# 07_USB_Interface.net
KiCad netlist of a schematic drawn in Altium Designer
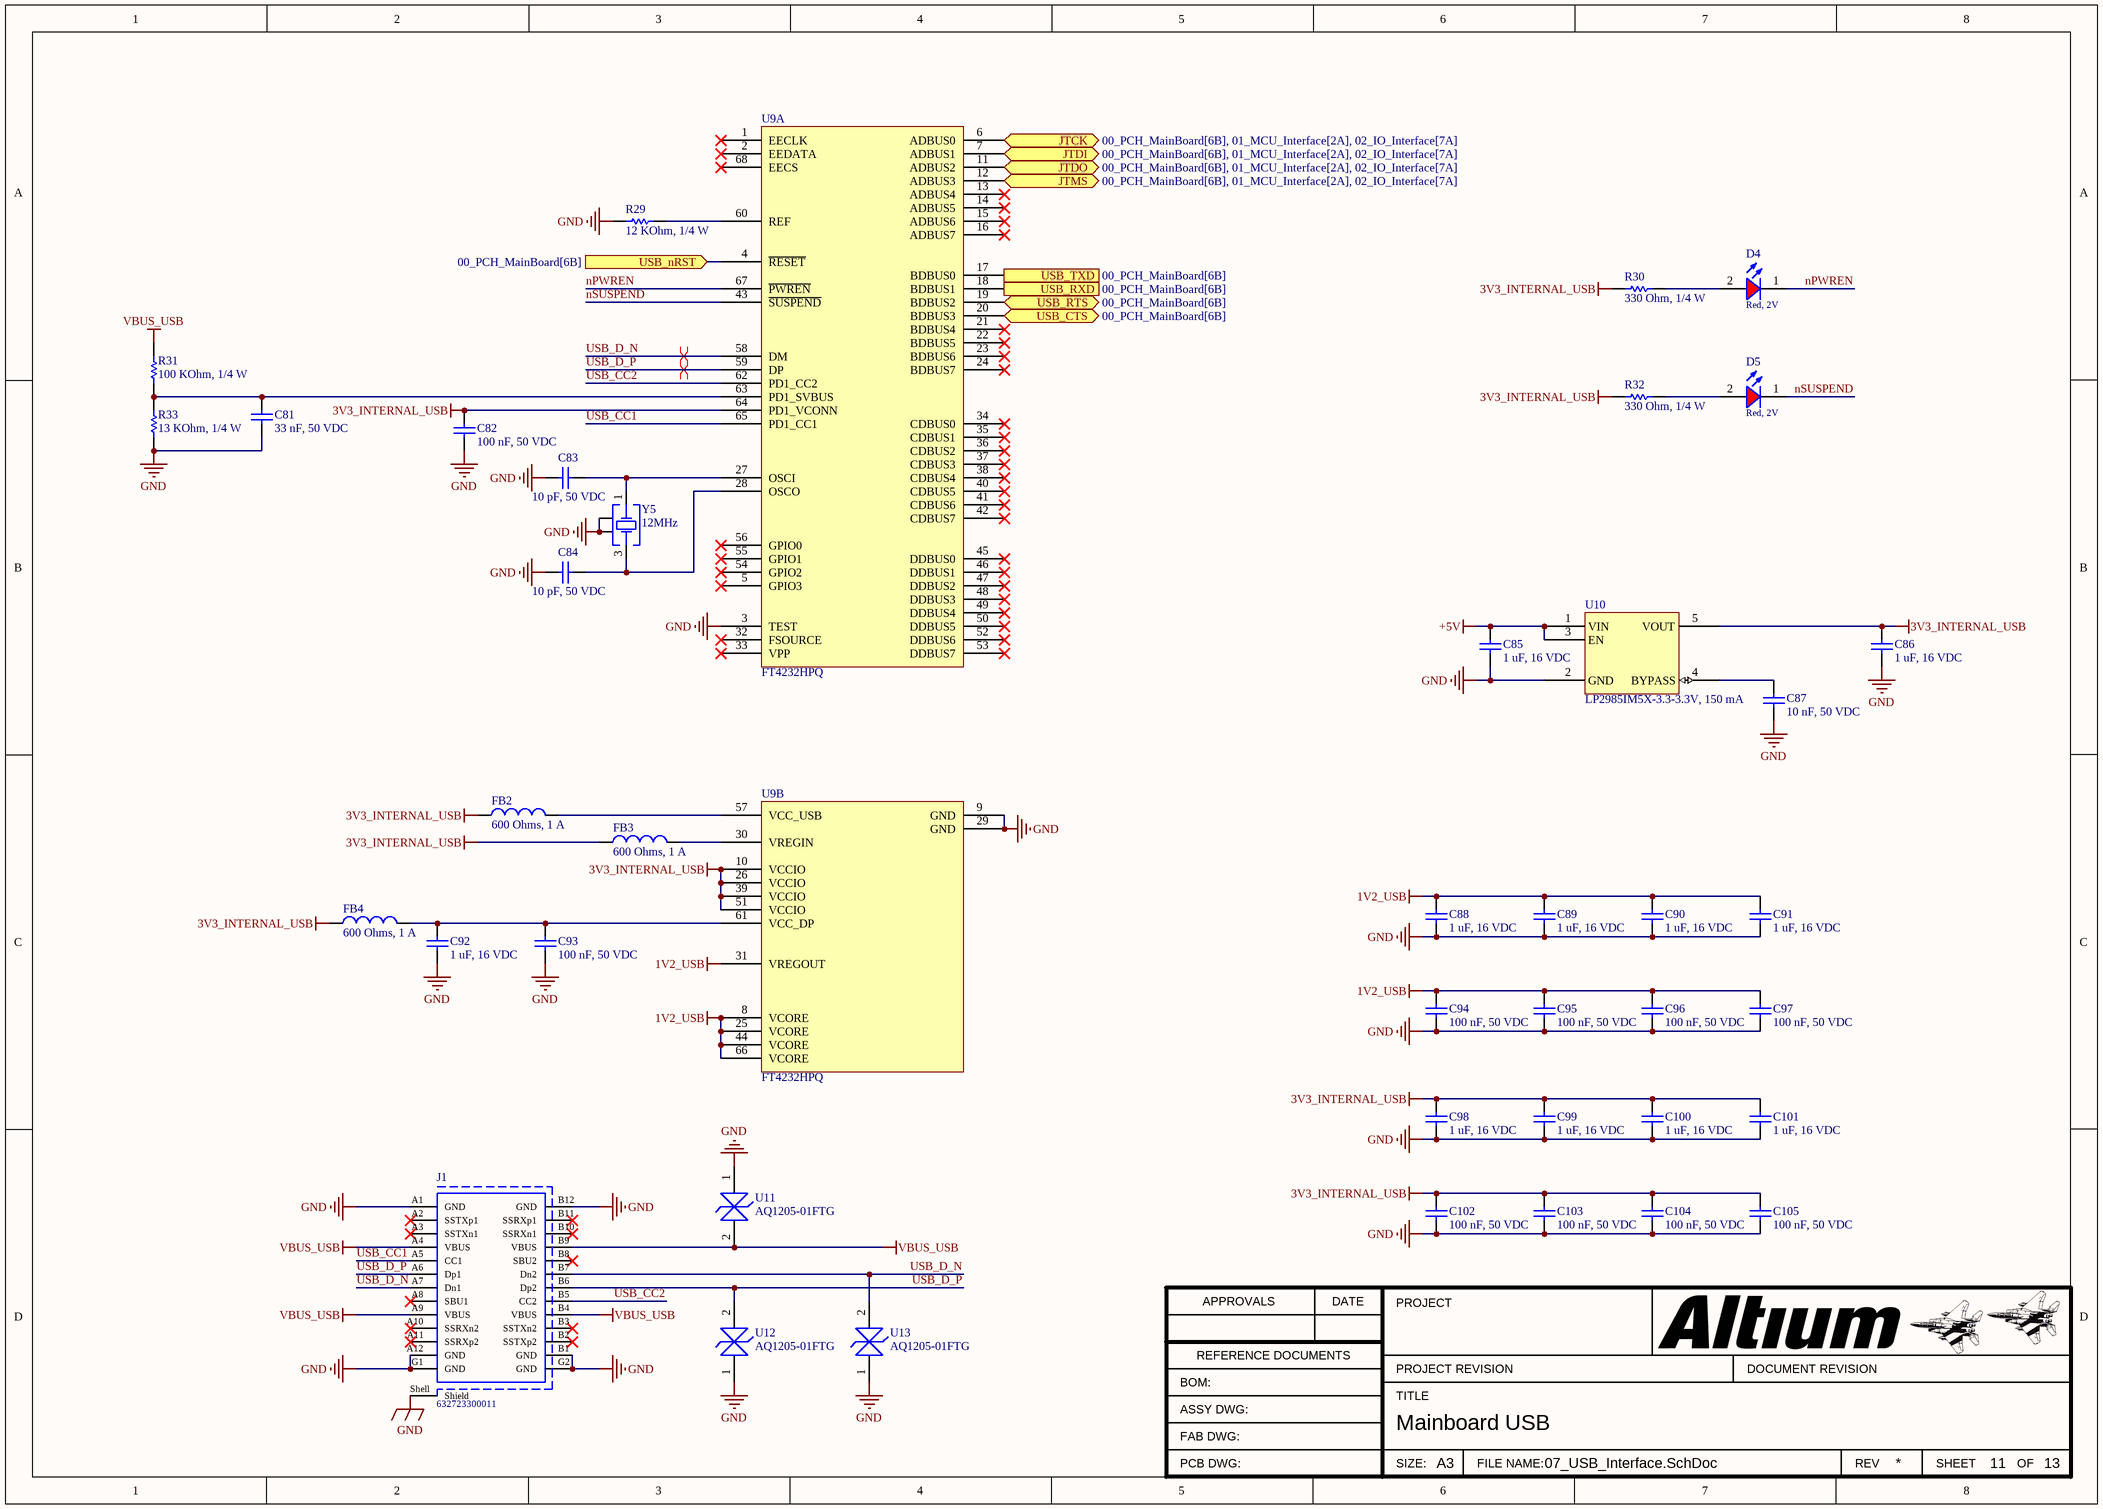
[diagram p0: 07_USB_Interface.SchDoc]

(export (version "E")
  (design (tool "Eeschema 10.0.6"))
  (components
    (comp (ref "C81")
      (value "33 nF, 50 VDC")
      (footprint "CAP_0603")
      (description "CAP, size 0603, 33 nF, 50 VDC")
      (fields (field (name "TOLERANCE") "+/-10%"))
      (libsource (lib "Altium_Ceramic_Cap") (part "0106033331050"))
    )
    (comp (ref "C82")
      (value "100 nF, 50 VDC")
      (footprint "CAP_0603")
      (description "CAP, size 0603, 100 nF, 50 VDC")
      (fields (field (name "TOLERANCE") "+/-10%"))
      (libsource (lib "Altium_Ceramic_Cap") (part "0106031041050"))
    )
    (comp (ref "C83")
      (value "10 pF, 50 VDC")
      (footprint "CAP_0603")
      (description "CAP, size 0603, 10 pF, 50 VDC")
      (fields (field (name "TOLERANCE") "+/-5%"))
      (libsource (lib "Altium_Ceramic_Cap") (part "0106031000550"))
    )
    (comp (ref "C84")
      (value "10 pF, 50 VDC")
      (footprint "CAP_0603")
      (description "CAP, size 0603, 10 pF, 50 VDC")
      (fields (field (name "TOLERANCE") "+/-5%"))
      (libsource (lib "Altium_Ceramic_Cap") (part "0106031000550"))
    )
    (comp (ref "C85")
      (value "1 uF, 16 VDC")
      (footprint "CAP_0603")
      (description "CAP, size 0603, 1 uF, 16 VDC")
      (fields (field (name "TOLERANCE") "+/-10%"))
      (libsource (lib "Altium_Ceramic_Cap") (part "0106031051016"))
    )
    (comp (ref "C86")
      (value "1 uF, 16 VDC")
      (footprint "CAP_0603")
      (description "CAP, size 0603, 1 uF, 16 VDC")
      (fields (field (name "TOLERANCE") "+/-10%"))
      (libsource (lib "Altium_Ceramic_Cap") (part "0106031051016"))
    )
    (comp (ref "C87")
      (value "10 nF, 50 VDC")
      (footprint "CAP_0603")
      (description "CAP, size 0603, 10 nF, 50 VDC")
      (fields (field (name "TOLERANCE") "+/-5%"))
      (libsource (lib "Altium_Ceramic_Cap") (part "0106031030550"))
    )
    (comp (ref "C88")
      (value "1 uF, 16 VDC")
      (footprint "CAP_0603")
      (description "CAP, size 0603, 1 uF, 16 VDC")
      (fields (field (name "TOLERANCE") "+/-10%"))
      (libsource (lib "Altium_Ceramic_Cap") (part "0106031051016"))
    )
    (comp (ref "C89")
      (value "1 uF, 16 VDC")
      (footprint "CAP_0603")
      (description "CAP, size 0603, 1 uF, 16 VDC")
      (fields (field (name "TOLERANCE") "+/-10%"))
      (libsource (lib "Altium_Ceramic_Cap") (part "0106031051016"))
    )
    (comp (ref "C90")
      (value "1 uF, 16 VDC")
      (footprint "CAP_0603")
      (description "CAP, size 0603, 1 uF, 16 VDC")
      (fields (field (name "TOLERANCE") "+/-10%"))
      (libsource (lib "Altium_Ceramic_Cap") (part "0106031051016"))
    )
    (comp (ref "C91")
      (value "1 uF, 16 VDC")
      (footprint "CAP_0603")
      (description "CAP, size 0603, 1 uF, 16 VDC")
      (fields (field (name "TOLERANCE") "+/-10%"))
      (libsource (lib "Altium_Ceramic_Cap") (part "0106031051016"))
    )
    (comp (ref "C92")
      (value "1 uF, 16 VDC")
      (footprint "CAP_0603")
      (description "CAP, size 0603, 1 uF, 16 VDC")
      (fields (field (name "TOLERANCE") "+/-10%"))
      (libsource (lib "Altium_Ceramic_Cap") (part "0106031051016"))
    )
    (comp (ref "C93")
      (value "100 nF, 50 VDC")
      (footprint "CAP_0603")
      (description "CAP, size 0603, 100 nF, 50 VDC")
      (fields (field (name "TOLERANCE") "+/-10%"))
      (libsource (lib "Altium_Ceramic_Cap") (part "0106031041050"))
    )
    (comp (ref "C94")
      (value "100 nF, 50 VDC")
      (footprint "CAP_0603")
      (description "CAP, size 0603, 100 nF, 50 VDC")
      (fields (field (name "TOLERANCE") "+/-10%"))
      (libsource (lib "Altium_Ceramic_Cap") (part "0106031041050"))
    )
    (comp (ref "C95")
      (value "100 nF, 50 VDC")
      (footprint "CAP_0603")
      (description "CAP, size 0603, 100 nF, 50 VDC")
      (fields (field (name "TOLERANCE") "+/-10%"))
      (libsource (lib "Altium_Ceramic_Cap") (part "0106031041050"))
    )
    (comp (ref "C96")
      (value "100 nF, 50 VDC")
      (footprint "CAP_0603")
      (description "CAP, size 0603, 100 nF, 50 VDC")
      (fields (field (name "TOLERANCE") "+/-10%"))
      (libsource (lib "Altium_Ceramic_Cap") (part "0106031041050"))
    )
    (comp (ref "C97")
      (value "100 nF, 50 VDC")
      (footprint "CAP_0603")
      (description "CAP, size 0603, 100 nF, 50 VDC")
      (fields (field (name "TOLERANCE") "+/-10%"))
      (libsource (lib "Altium_Ceramic_Cap") (part "0106031041050"))
    )
    (comp (ref "C98")
      (value "1 uF, 16 VDC")
      (footprint "CAP_0603")
      (description "CAP, size 0603, 1 uF, 16 VDC")
      (fields (field (name "TOLERANCE") "+/-10%"))
      (libsource (lib "Altium_Ceramic_Cap") (part "0106031051016"))
    )
    (comp (ref "C99")
      (value "1 uF, 16 VDC")
      (footprint "CAP_0603")
      (description "CAP, size 0603, 1 uF, 16 VDC")
      (fields (field (name "TOLERANCE") "+/-10%"))
      (libsource (lib "Altium_Ceramic_Cap") (part "0106031051016"))
    )
    (comp (ref "C100")
      (value "1 uF, 16 VDC")
      (footprint "CAP_0603")
      (description "CAP, size 0603, 1 uF, 16 VDC")
      (fields (field (name "TOLERANCE") "+/-10%"))
      (libsource (lib "Altium_Ceramic_Cap") (part "0106031051016"))
    )
    (comp (ref "C101")
      (value "1 uF, 16 VDC")
      (footprint "CAP_0603")
      (description "CAP, size 0603, 1 uF, 16 VDC")
      (fields (field (name "TOLERANCE") "+/-10%"))
      (libsource (lib "Altium_Ceramic_Cap") (part "0106031051016"))
    )
    (comp (ref "C102")
      (value "100 nF, 50 VDC")
      (footprint "CAP_0603")
      (description "CAP, size 0603, 100 nF, 50 VDC")
      (fields (field (name "TOLERANCE") "+/-10%"))
      (libsource (lib "Altium_Ceramic_Cap") (part "0106031041050"))
    )
    (comp (ref "C103")
      (value "100 nF, 50 VDC")
      (footprint "CAP_0603")
      (description "CAP, size 0603, 100 nF, 50 VDC")
      (fields (field (name "TOLERANCE") "+/-10%"))
      (libsource (lib "Altium_Ceramic_Cap") (part "0106031041050"))
    )
    (comp (ref "C104")
      (value "100 nF, 50 VDC")
      (footprint "CAP_0603")
      (description "CAP, size 0603, 100 nF, 50 VDC")
      (fields (field (name "TOLERANCE") "+/-10%"))
      (libsource (lib "Altium_Ceramic_Cap") (part "0106031041050"))
    )
    (comp (ref "C105")
      (value "100 nF, 50 VDC")
      (footprint "CAP_0603")
      (description "CAP, size 0603, 100 nF, 50 VDC")
      (fields (field (name "TOLERANCE") "+/-10%"))
      (libsource (lib "Altium_Ceramic_Cap") (part "0106031041050"))
    )
    (comp (ref "D4")
      (value "Red, 2V")
      (footprint "WL-SMCW_0603_H=0.7mm")
      (description "WL-SMCW SMT Mono-color Chip LED Blur, size 0603, Red, 2V, 140deg")
      (libsource (lib "Altium_LED") (part "160603RedBlur"))
    )
    (comp (ref "D5")
      (value "Red, 2V")
      (footprint "WL-SMCW_0603_H=0.7mm")
      (description "WL-SMCW SMT Mono-color Chip LED Blur, size 0603, Red, 2V, 140deg")
      (libsource (lib "Altium_LED") (part "160603RedBlur"))
    )
    (comp (ref "FB2")
      (value "600 Ohms, 1 A")
      (footprint "FER_0603")
      (description "Ferrite, 0603, 600 Ohms, 1 A")
      (fields (field (name "TOLERANCE") "+/-25%"))
      (libsource (lib "Altium_Ferrite_Bead") (part "03060360110225"))
    )
    (comp (ref "FB3")
      (value "600 Ohms, 1 A")
      (footprint "FER_0603")
      (description "Ferrite, 0603, 600 Ohms, 1 A")
      (fields (field (name "TOLERANCE") "+/-25%"))
      (libsource (lib "Altium_Ferrite_Bead") (part "03060360110225"))
    )
    (comp (ref "FB4")
      (value "600 Ohms, 1 A")
      (footprint "FER_0603")
      (description "Ferrite, 0603, 600 Ohms, 1 A")
      (fields (field (name "TOLERANCE") "+/-25%"))
      (libsource (lib "Altium_Ferrite_Bead") (part "03060360110225"))
    )
    (comp (ref "J1")
      (value "632723300011")
      (footprint "632723300011")
      (description "USB 3.1 Type C Receptacle WR-COM, Horizontal, SMT / THT")
      (fields (field (name "PUBLISHER") "Wurth Elektronik"))
      (libsource (lib "Altium_USB") (part "632723300011"))
    )
    (comp (ref "R29")
      (value "12 KOhm, 1/4 W")
      (footprint "resistor_0603")
      (description "RES, size 0603, 12 KOhm, 1/4 W")
      (libsource (lib "Altium_Resistor") (part "0006031231"))
    )
    (comp (ref "R30")
      (value "330 Ohm, 1/4 W")
      (footprint "resistor_0603")
      (description "RES, size 0603, 330 Ohm, 1/4 W")
      (libsource (lib "Altium_Resistor") (part "0006033311"))
    )
    (comp (ref "R31")
      (value "100 KOhm, 1/4 W")
      (footprint "resistor_0603")
      (description "RES, size 0603, 100 KOhm, 1/4 W")
      (libsource (lib "Altium_Resistor") (part "0006031041"))
    )
    (comp (ref "R32")
      (value "330 Ohm, 1/4 W")
      (footprint "resistor_0603")
      (description "RES, size 0603, 330 Ohm, 1/4 W")
      (libsource (lib "Altium_Resistor") (part "0006033311"))
    )
    (comp (ref "R33")
      (value "13 KOhm, 1/4 W")
      (footprint "resistor_0603")
      (description "RES, size 0603, 13 KOhm, 1/4 W")
      (libsource (lib "Altium_Resistor") (part "0006031331"))
    )
    (comp (ref "U9")
      (value "FT4232HPQ")
      (footprint "FT4232HPQ")
      (description "USB Interface IC USB Bridge Type-C 3.0 32-Bit 8kB 48kB")
      (fields (field (name "MANUFACTURER") "FTDI"))
      (libsource (lib "Altium_MCU") (part "FT4232HPQ"))
    )
    (comp (ref "U10")
      (value "LP2985IM5X-3.3-3.3V, 150 mA")
      (footprint "SOT23-5")
      (description "Out: 3.3V, 150 mA max; In: 2.5 V to 16 V; Pacakge: SOT-23-5")
      (fields
        (field (name "MANUFACTURER") "Texas Instruments")
        (field (name "MANUFACTURER PART NUMBER") "LP2985IM5X-3.3")
      )
      (libsource (lib "Altium_Power_Supply_IC") (part "LP2985IM5X-3.3/NOPBSOT23"))
    )
    (comp (ref "U11")
      (value "AQ1205-01FTG")
      (footprint "SOD323")
      (description "ESD Suppressors / TVS Diodes 5V 7A 30kV SOD323 Bi-dir TVS")
      (libsource (lib "Altium_ESD") (part "AQ1205-01FTG"))
    )
    (comp (ref "U12")
      (value "AQ1205-01FTG")
      (footprint "SOD323")
      (description "ESD Suppressors / TVS Diodes 5V 7A 30kV SOD323 Bi-dir TVS")
      (libsource (lib "Altium_ESD") (part "AQ1205-01FTG"))
    )
    (comp (ref "U13")
      (value "AQ1205-01FTG")
      (footprint "SOD323")
      (description "ESD Suppressors / TVS Diodes 5V 7A 30kV SOD323 Bi-dir TVS")
      (libsource (lib "Altium_ESD") (part "AQ1205-01FTG"))
    )
    (comp (ref "Y5")
      (value "12MHz")
      (footprint "WE-XTAL_CFPX-180")
      (description "WE-XTAL Quartz Crystal, SMT, CFPX-180, 12MHz, +/-30ppm")
      (fields
        (field (name "MANUFACTURER PART NUMBER") "NX3225SA-12MHZ-STD-CSR-6")
        (field (name "MANUFACTURER") "NDK")
      )
      (libsource (lib "Altium_XTAL") (part "073525126010"))
    )
  )
  (nets
    (net (code "1") (name "+5V") (class "Default")
      (node (ref "C85") (pin "2") (pinfunction "2_2") (pintype "passive"))
      (node (ref "U10") (pin "1") (pinfunction "VIN_1") (pintype "power_in"))
      (node (ref "U10") (pin "3") (pinfunction "EN_3") (pintype "passive"))
    )
    (net (code "2") (name "/JTCK") (class "Default")
      (node (ref "U9") (pin "6") (pinfunction "ADBUS0_6") (pintype "passive"))
    )
    (net (code "3") (name "/JTDI") (class "Default")
      (node (ref "U9") (pin "7") (pinfunction "ADBUS1_7") (pintype "passive"))
    )
    (net (code "4") (name "/JTDO") (class "Default")
      (node (ref "U9") (pin "11") (pinfunction "ADBUS2_11") (pintype "passive"))
    )
    (net (code "5") (name "/JTMS") (class "Default")
      (node (ref "U9") (pin "12") (pinfunction "ADBUS3_12") (pintype "passive"))
    )
    (net (code "6") (name "/USB_CC1") (class "Default")
      (node (ref "J1") (pin "A5") (pinfunction "CC1_A5") (pintype "passive"))
      (node (ref "U9") (pin "65") (pinfunction "PD1_CC1_65") (pintype "passive"))
    )
    (net (code "7") (name "/USB_CC2") (class "Default")
      (node (ref "J1") (pin "B5") (pinfunction "CC2_B5") (pintype "passive"))
      (node (ref "U9") (pin "62") (pinfunction "PD1_CC2_62") (pintype "passive"))
    )
    (net (code "8") (name "/USB_CTS") (class "Default")
      (node (ref "U9") (pin "20") (pinfunction "BDBUS3_20") (pintype "passive"))
    )
    (net (code "9") (name "/USB_D_N") (class "Default")
      (node (ref "J1") (pin "A7") (pinfunction "Dn1_A7") (pintype "passive"))
      (node (ref "J1") (pin "B7") (pinfunction "Dn2_B7") (pintype "passive"))
      (node (ref "U13") (pin "2") (pinfunction "2_2") (pintype "passive"))
      (node (ref "U9") (pin "58") (pinfunction "DM_58") (pintype "passive"))
    )
    (net (code "10") (name "/USB_D_P") (class "Default")
      (node (ref "J1") (pin "A6") (pinfunction "Dp1_A6") (pintype "passive"))
      (node (ref "J1") (pin "B6") (pinfunction "Dp2_B6") (pintype "passive"))
      (node (ref "U12") (pin "2") (pinfunction "2_2") (pintype "passive"))
      (node (ref "U9") (pin "59") (pinfunction "DP_59") (pintype "passive"))
    )
    (net (code "11") (name "/USB_RTS") (class "Default")
      (node (ref "U9") (pin "19") (pinfunction "BDBUS2_19") (pintype "passive"))
    )
    (net (code "12") (name "/USB_RXD") (class "Default")
      (node (ref "U9") (pin "18") (pinfunction "BDBUS1_18") (pintype "passive"))
    )
    (net (code "13") (name "/USB_TXD") (class "Default")
      (node (ref "U9") (pin "17") (pinfunction "BDBUS0_17") (pintype "passive"))
    )
    (net (code "14") (name "/USB_nRST") (class "Default")
      (node (ref "U9") (pin "4") (pinfunction "~{RESET}_4") (pintype "passive"))
    )
    (net (code "15") (name "/nPWREN") (class "Default")
      (node (ref "D4") (pin "1") (pinfunction "K_1") (pintype "passive"))
      (node (ref "U9") (pin "67") (pinfunction "~{PWREN}_67") (pintype "passive"))
    )
    (net (code "16") (name "/nSUSPEND") (class "Default")
      (node (ref "D5") (pin "1") (pinfunction "K_1") (pintype "passive"))
      (node (ref "U9") (pin "43") (pinfunction "~{SUSPEND}_43") (pintype "passive"))
    )
    (net (code "17") (name "1V2_USB") (class "Default")
      (node (ref "C88") (pin "2") (pinfunction "2_2") (pintype "passive"))
      (node (ref "C89") (pin "2") (pinfunction "2_2") (pintype "passive"))
      (node (ref "C90") (pin "2") (pinfunction "2_2") (pintype "passive"))
      (node (ref "C91") (pin "2") (pinfunction "2_2") (pintype "passive"))
      (node (ref "C94") (pin "2") (pinfunction "2_2") (pintype "passive"))
      (node (ref "C95") (pin "2") (pinfunction "2_2") (pintype "passive"))
      (node (ref "C96") (pin "2") (pinfunction "2_2") (pintype "passive"))
      (node (ref "C97") (pin "2") (pinfunction "2_2") (pintype "passive"))
      (node (ref "U9") (pin "25") (pinfunction "VCORE_25") (pintype "passive"))
      (node (ref "U9") (pin "31") (pinfunction "VREGOUT_31") (pintype "passive"))
      (node (ref "U9") (pin "44") (pinfunction "VCORE_44") (pintype "passive"))
      (node (ref "U9") (pin "66") (pinfunction "VCORE_66") (pintype "passive"))
      (node (ref "U9") (pin "8") (pinfunction "VCORE_8") (pintype "passive"))
    )
    (net (code "18") (name "3V3_INTERNAL_USB") (class "Default")
      (node (ref "C100") (pin "2") (pinfunction "2_2") (pintype "passive"))
      (node (ref "C101") (pin "2") (pinfunction "2_2") (pintype "passive"))
      (node (ref "C102") (pin "2") (pinfunction "2_2") (pintype "passive"))
      (node (ref "C103") (pin "2") (pinfunction "2_2") (pintype "passive"))
      (node (ref "C104") (pin "2") (pinfunction "2_2") (pintype "passive"))
      (node (ref "C105") (pin "2") (pinfunction "2_2") (pintype "passive"))
      (node (ref "C82") (pin "2") (pinfunction "2_2") (pintype "passive"))
      (node (ref "C86") (pin "2") (pinfunction "2_2") (pintype "passive"))
      (node (ref "C98") (pin "2") (pinfunction "2_2") (pintype "passive"))
      (node (ref "C99") (pin "2") (pinfunction "2_2") (pintype "passive"))
      (node (ref "FB2") (pin "1") (pinfunction "1_1") (pintype "passive"))
      (node (ref "FB3") (pin "1") (pinfunction "1_1") (pintype "passive"))
      (node (ref "FB4") (pin "1") (pinfunction "1_1") (pintype "passive"))
      (node (ref "R30") (pin "2") (pinfunction "2_2") (pintype "passive"))
      (node (ref "R32") (pin "2") (pinfunction "2_2") (pintype "passive"))
      (node (ref "U10") (pin "5") (pinfunction "VOUT_5") (pintype "power_in"))
      (node (ref "U9") (pin "10") (pinfunction "VCCIO_10") (pintype "passive"))
      (node (ref "U9") (pin "26") (pinfunction "VCCIO_26") (pintype "passive"))
      (node (ref "U9") (pin "39") (pinfunction "VCCIO_39") (pintype "passive"))
      (node (ref "U9") (pin "51") (pinfunction "VCCIO_51") (pintype "passive"))
      (node (ref "U9") (pin "64") (pinfunction "PD1_VCONN_64") (pintype "passive"))
    )
    (net (code "19") (name "GND") (class "Default")
      (node (ref "C100") (pin "1") (pinfunction "1_1") (pintype "passive"))
      (node (ref "C101") (pin "1") (pinfunction "1_1") (pintype "passive"))
      (node (ref "C102") (pin "1") (pinfunction "1_1") (pintype "passive"))
      (node (ref "C103") (pin "1") (pinfunction "1_1") (pintype "passive"))
      (node (ref "C104") (pin "1") (pinfunction "1_1") (pintype "passive"))
      (node (ref "C105") (pin "1") (pinfunction "1_1") (pintype "passive"))
      (node (ref "C81") (pin "1") (pinfunction "1_1") (pintype "passive"))
      (node (ref "C82") (pin "1") (pinfunction "1_1") (pintype "passive"))
      (node (ref "C83") (pin "1") (pinfunction "1_1") (pintype "passive"))
      (node (ref "C84") (pin "1") (pinfunction "1_1") (pintype "passive"))
      (node (ref "C85") (pin "1") (pinfunction "1_1") (pintype "passive"))
      (node (ref "C86") (pin "1") (pinfunction "1_1") (pintype "passive"))
      (node (ref "C87") (pin "1") (pinfunction "1_1") (pintype "passive"))
      (node (ref "C88") (pin "1") (pinfunction "1_1") (pintype "passive"))
      (node (ref "C89") (pin "1") (pinfunction "1_1") (pintype "passive"))
      (node (ref "C90") (pin "1") (pinfunction "1_1") (pintype "passive"))
      (node (ref "C91") (pin "1") (pinfunction "1_1") (pintype "passive"))
      (node (ref "C92") (pin "1") (pinfunction "1_1") (pintype "passive"))
      (node (ref "C93") (pin "1") (pinfunction "1_1") (pintype "passive"))
      (node (ref "C94") (pin "1") (pinfunction "1_1") (pintype "passive"))
      (node (ref "C95") (pin "1") (pinfunction "1_1") (pintype "passive"))
      (node (ref "C96") (pin "1") (pinfunction "1_1") (pintype "passive"))
      (node (ref "C97") (pin "1") (pinfunction "1_1") (pintype "passive"))
      (node (ref "C98") (pin "1") (pinfunction "1_1") (pintype "passive"))
      (node (ref "C99") (pin "1") (pinfunction "1_1") (pintype "passive"))
      (node (ref "J1") (pin "A1") (pinfunction "GND_A1") (pintype "passive"))
      (node (ref "J1") (pin "A12") (pinfunction "GND_A12") (pintype "passive"))
      (node (ref "J1") (pin "B1") (pinfunction "GND_B1") (pintype "passive"))
      (node (ref "J1") (pin "B12") (pinfunction "GND_B12") (pintype "passive"))
      (node (ref "J1") (pin "G1") (pinfunction "GND_G1") (pintype "passive"))
      (node (ref "J1") (pin "G2") (pinfunction "GND_G2") (pintype "passive"))
      (node (ref "J1") (pin "Shell") (pinfunction "Shield_Shell") (pintype "passive"))
      (node (ref "R29") (pin "1") (pinfunction "1_1") (pintype "passive"))
      (node (ref "R33") (pin "1") (pinfunction "1_1") (pintype "passive"))
      (node (ref "U10") (pin "2") (pinfunction "GND_2") (pintype "passive"))
      (node (ref "U11") (pin "1") (pinfunction "1_1") (pintype "passive"))
      (node (ref "U12") (pin "1") (pinfunction "1_1") (pintype "passive"))
      (node (ref "U13") (pin "1") (pinfunction "1_1") (pintype "passive"))
      (node (ref "U9") (pin "29") (pinfunction "GND_29") (pintype "passive"))
      (node (ref "U9") (pin "3") (pinfunction "TEST_3") (pintype "passive"))
      (node (ref "U9") (pin "9") (pinfunction "GND_9") (pintype "passive"))
      (node (ref "Y5") (pin "2") (pinfunction "GND_2") (pintype "passive"))
      (node (ref "Y5") (pin "4") (pinfunction "GND_4") (pintype "passive"))
    )
    (net (code "20") (name "Net-(D4-A)") (class "Default")
      (node (ref "D4") (pin "2") (pinfunction "A_2") (pintype "passive"))
      (node (ref "R30") (pin "1") (pinfunction "1_1") (pintype "passive"))
    )
    (net (code "21") (name "Net-(D5-A)") (class "Default")
      (node (ref "D5") (pin "2") (pinfunction "A_2") (pintype "passive"))
      (node (ref "R32") (pin "1") (pinfunction "1_1") (pintype "passive"))
    )
    (net (code "22") (name "Net-(U9A-OSCI)") (class "Default")
      (node (ref "C83") (pin "2") (pinfunction "2_2") (pintype "passive"))
      (node (ref "U9") (pin "27") (pinfunction "OSCI_27") (pintype "passive"))
      (node (ref "Y5") (pin "1") (pinfunction "Crystal_1") (pintype "passive"))
    )
    (net (code "23") (name "Net-(U9A-OSCO)") (class "Default")
      (node (ref "C84") (pin "2") (pinfunction "2_2") (pintype "passive"))
      (node (ref "U9") (pin "28") (pinfunction "OSCO_28") (pintype "passive"))
      (node (ref "Y5") (pin "3") (pinfunction "Crystal_3") (pintype "passive"))
    )
    (net (code "24") (name "Net-(U9A-PD1_SVBUS)") (class "Default")
      (node (ref "C81") (pin "2") (pinfunction "2_2") (pintype "passive"))
      (node (ref "R31") (pin "1") (pinfunction "1_1") (pintype "passive"))
      (node (ref "R33") (pin "2") (pinfunction "2_2") (pintype "passive"))
      (node (ref "U9") (pin "63") (pinfunction "PD1_SVBUS_63") (pintype "passive"))
    )
    (net (code "25") (name "Net-(U9A-REF)") (class "Default")
      (node (ref "R29") (pin "2") (pinfunction "2_2") (pintype "passive"))
      (node (ref "U9") (pin "60") (pinfunction "REF_60") (pintype "passive"))
    )
    (net (code "26") (name "Net-(U9B-VCC_DP)") (class "Default")
      (node (ref "C92") (pin "2") (pinfunction "2_2") (pintype "passive"))
      (node (ref "C93") (pin "2") (pinfunction "2_2") (pintype "passive"))
      (node (ref "FB4") (pin "2") (pinfunction "2_2") (pintype "passive"))
      (node (ref "U9") (pin "61") (pinfunction "VCC_DP_61") (pintype "passive"))
    )
    (net (code "27") (name "Net-(U9B-VCC_USB)") (class "Default")
      (node (ref "FB2") (pin "2") (pinfunction "2_2") (pintype "passive"))
      (node (ref "U9") (pin "57") (pinfunction "VCC_USB_57") (pintype "passive"))
    )
    (net (code "28") (name "Net-(U9B-VREGIN)") (class "Default")
      (node (ref "FB3") (pin "2") (pinfunction "2_2") (pintype "passive"))
      (node (ref "U9") (pin "30") (pinfunction "VREGIN_30") (pintype "passive"))
    )
    (net (code "29") (name "Net-(U10-BYPASS)") (class "Default")
      (node (ref "C87") (pin "2") (pinfunction "2_2") (pintype "passive"))
      (node (ref "U10") (pin "4") (pinfunction "BYPASS_4") (pintype "bidirectional"))
    )
    (net (code "30") (name "VBUS_USB") (class "Default")
      (node (ref "J1") (pin "A4") (pinfunction "VBUS_A4") (pintype "passive"))
      (node (ref "J1") (pin "A9") (pinfunction "VBUS_A9") (pintype "passive"))
      (node (ref "J1") (pin "B4") (pinfunction "VBUS_B4") (pintype "passive"))
      (node (ref "J1") (pin "B9") (pinfunction "VBUS_B9") (pintype "passive"))
      (node (ref "R31") (pin "2") (pinfunction "2_2") (pintype "passive"))
      (node (ref "U11") (pin "2") (pinfunction "2_2") (pintype "passive"))
    )
    (net (code "31") (name "unconnected-(J1-SBU1-PadA8)") (class "Default")
      (node (ref "J1") (pin "A8") (pinfunction "SBU1_A8") (pintype "passive+no_connect"))
    )
    (net (code "32") (name "unconnected-(J1-SBU2-PadB8)") (class "Default")
      (node (ref "J1") (pin "B8") (pinfunction "SBU2_B8") (pintype "passive+no_connect"))
    )
    (net (code "33") (name "unconnected-(J1-SSRXn1-PadB10)") (class "Default")
      (node (ref "J1") (pin "B10") (pinfunction "SSRXn1_B10") (pintype "passive+no_connect"))
    )
    (net (code "34") (name "unconnected-(J1-SSRXn2-PadA10)") (class "Default")
      (node (ref "J1") (pin "A10") (pinfunction "SSRXn2_A10") (pintype "passive+no_connect"))
    )
    (net (code "35") (name "unconnected-(J1-SSRXp1-PadB11)") (class "Default")
      (node (ref "J1") (pin "B11") (pinfunction "SSRXp1_B11") (pintype "passive+no_connect"))
    )
    (net (code "36") (name "unconnected-(J1-SSRXp2-PadA11)") (class "Default")
      (node (ref "J1") (pin "A11") (pinfunction "SSRXp2_A11") (pintype "passive+no_connect"))
    )
    (net (code "37") (name "unconnected-(J1-SSTXn1-PadA3)") (class "Default")
      (node (ref "J1") (pin "A3") (pinfunction "SSTXn1_A3") (pintype "passive+no_connect"))
    )
    (net (code "38") (name "unconnected-(J1-SSTXn2-PadB3)") (class "Default")
      (node (ref "J1") (pin "B3") (pinfunction "SSTXn2_B3") (pintype "passive+no_connect"))
    )
    (net (code "39") (name "unconnected-(J1-SSTXp1-PadA2)") (class "Default")
      (node (ref "J1") (pin "A2") (pinfunction "SSTXp1_A2") (pintype "passive+no_connect"))
    )
    (net (code "40") (name "unconnected-(J1-SSTXp2-PadB2)") (class "Default")
      (node (ref "J1") (pin "B2") (pinfunction "SSTXp2_B2") (pintype "passive+no_connect"))
    )
    (net (code "41") (name "unconnected-(U9A-ADBUS4-Pad13)") (class "Default")
      (node (ref "U9") (pin "13") (pinfunction "ADBUS4_13") (pintype "passive+no_connect"))
    )
    (net (code "42") (name "unconnected-(U9A-ADBUS5-Pad14)") (class "Default")
      (node (ref "U9") (pin "14") (pinfunction "ADBUS5_14") (pintype "passive+no_connect"))
    )
    (net (code "43") (name "unconnected-(U9A-ADBUS6-Pad15)") (class "Default")
      (node (ref "U9") (pin "15") (pinfunction "ADBUS6_15") (pintype "passive+no_connect"))
    )
    (net (code "44") (name "unconnected-(U9A-ADBUS7-Pad16)") (class "Default")
      (node (ref "U9") (pin "16") (pinfunction "ADBUS7_16") (pintype "passive+no_connect"))
    )
    (net (code "45") (name "unconnected-(U9A-BDBUS4-Pad21)") (class "Default")
      (node (ref "U9") (pin "21") (pinfunction "BDBUS4_21") (pintype "passive+no_connect"))
    )
    (net (code "46") (name "unconnected-(U9A-BDBUS5-Pad22)") (class "Default")
      (node (ref "U9") (pin "22") (pinfunction "BDBUS5_22") (pintype "passive+no_connect"))
    )
    (net (code "47") (name "unconnected-(U9A-BDBUS6-Pad23)") (class "Default")
      (node (ref "U9") (pin "23") (pinfunction "BDBUS6_23") (pintype "passive+no_connect"))
    )
    (net (code "48") (name "unconnected-(U9A-BDBUS7-Pad24)") (class "Default")
      (node (ref "U9") (pin "24") (pinfunction "BDBUS7_24") (pintype "passive+no_connect"))
    )
    (net (code "49") (name "unconnected-(U9A-CDBUS0-Pad34)") (class "Default")
      (node (ref "U9") (pin "34") (pinfunction "CDBUS0_34") (pintype "passive+no_connect"))
    )
    (net (code "50") (name "unconnected-(U9A-CDBUS1-Pad35)") (class "Default")
      (node (ref "U9") (pin "35") (pinfunction "CDBUS1_35") (pintype "passive+no_connect"))
    )
    (net (code "51") (name "unconnected-(U9A-CDBUS2-Pad36)") (class "Default")
      (node (ref "U9") (pin "36") (pinfunction "CDBUS2_36") (pintype "passive+no_connect"))
    )
    (net (code "52") (name "unconnected-(U9A-CDBUS3-Pad37)") (class "Default")
      (node (ref "U9") (pin "37") (pinfunction "CDBUS3_37") (pintype "passive+no_connect"))
    )
    (net (code "53") (name "unconnected-(U9A-CDBUS4-Pad38)") (class "Default")
      (node (ref "U9") (pin "38") (pinfunction "CDBUS4_38") (pintype "passive+no_connect"))
    )
    (net (code "54") (name "unconnected-(U9A-CDBUS5-Pad40)") (class "Default")
      (node (ref "U9") (pin "40") (pinfunction "CDBUS5_40") (pintype "passive+no_connect"))
    )
    (net (code "55") (name "unconnected-(U9A-CDBUS6-Pad41)") (class "Default")
      (node (ref "U9") (pin "41") (pinfunction "CDBUS6_41") (pintype "passive+no_connect"))
    )
    (net (code "56") (name "unconnected-(U9A-CDBUS7-Pad42)") (class "Default")
      (node (ref "U9") (pin "42") (pinfunction "CDBUS7_42") (pintype "passive+no_connect"))
    )
    (net (code "57") (name "unconnected-(U9A-DDBUS0-Pad45)") (class "Default")
      (node (ref "U9") (pin "45") (pinfunction "DDBUS0_45") (pintype "passive+no_connect"))
    )
    (net (code "58") (name "unconnected-(U9A-DDBUS1-Pad46)") (class "Default")
      (node (ref "U9") (pin "46") (pinfunction "DDBUS1_46") (pintype "passive+no_connect"))
    )
    (net (code "59") (name "unconnected-(U9A-DDBUS2-Pad47)") (class "Default")
      (node (ref "U9") (pin "47") (pinfunction "DDBUS2_47") (pintype "passive+no_connect"))
    )
    (net (code "60") (name "unconnected-(U9A-DDBUS3-Pad48)") (class "Default")
      (node (ref "U9") (pin "48") (pinfunction "DDBUS3_48") (pintype "passive+no_connect"))
    )
    (net (code "61") (name "unconnected-(U9A-DDBUS4-Pad49)") (class "Default")
      (node (ref "U9") (pin "49") (pinfunction "DDBUS4_49") (pintype "passive+no_connect"))
    )
    (net (code "62") (name "unconnected-(U9A-DDBUS5-Pad50)") (class "Default")
      (node (ref "U9") (pin "50") (pinfunction "DDBUS5_50") (pintype "passive+no_connect"))
    )
    (net (code "63") (name "unconnected-(U9A-DDBUS6-Pad52)") (class "Default")
      (node (ref "U9") (pin "52") (pinfunction "DDBUS6_52") (pintype "passive+no_connect"))
    )
    (net (code "64") (name "unconnected-(U9A-DDBUS7-Pad53)") (class "Default")
      (node (ref "U9") (pin "53") (pinfunction "DDBUS7_53") (pintype "passive+no_connect"))
    )
    (net (code "65") (name "unconnected-(U9A-EECLK-Pad1)") (class "Default")
      (node (ref "U9") (pin "1") (pinfunction "EECLK_1") (pintype "passive+no_connect"))
    )
    (net (code "66") (name "unconnected-(U9A-EECS-Pad68)") (class "Default")
      (node (ref "U9") (pin "68") (pinfunction "EECS_68") (pintype "passive+no_connect"))
    )
    (net (code "67") (name "unconnected-(U9A-EEDATA-Pad2)") (class "Default")
      (node (ref "U9") (pin "2") (pinfunction "EEDATA_2") (pintype "passive+no_connect"))
    )
    (net (code "68") (name "unconnected-(U9A-FSOURCE-Pad32)") (class "Default")
      (node (ref "U9") (pin "32") (pinfunction "FSOURCE_32") (pintype "passive+no_connect"))
    )
    (net (code "69") (name "unconnected-(U9A-GPIO0-Pad56)") (class "Default")
      (node (ref "U9") (pin "56") (pinfunction "GPIO0_56") (pintype "passive+no_connect"))
    )
    (net (code "70") (name "unconnected-(U9A-GPIO1-Pad55)") (class "Default")
      (node (ref "U9") (pin "55") (pinfunction "GPIO1_55") (pintype "passive+no_connect"))
    )
    (net (code "71") (name "unconnected-(U9A-GPIO2-Pad54)") (class "Default")
      (node (ref "U9") (pin "54") (pinfunction "GPIO2_54") (pintype "passive+no_connect"))
    )
    (net (code "72") (name "unconnected-(U9A-GPIO3-Pad5)") (class "Default")
      (node (ref "U9") (pin "5") (pinfunction "GPIO3_5") (pintype "passive+no_connect"))
    )
    (net (code "73") (name "unconnected-(U9A-VPP-Pad33)") (class "Default")
      (node (ref "U9") (pin "33") (pinfunction "VPP_33") (pintype "passive+no_connect"))
    )
  )
)
